# Digital_Attenuator.net
KiCad netlist of a schematic drawn in Altium Designer
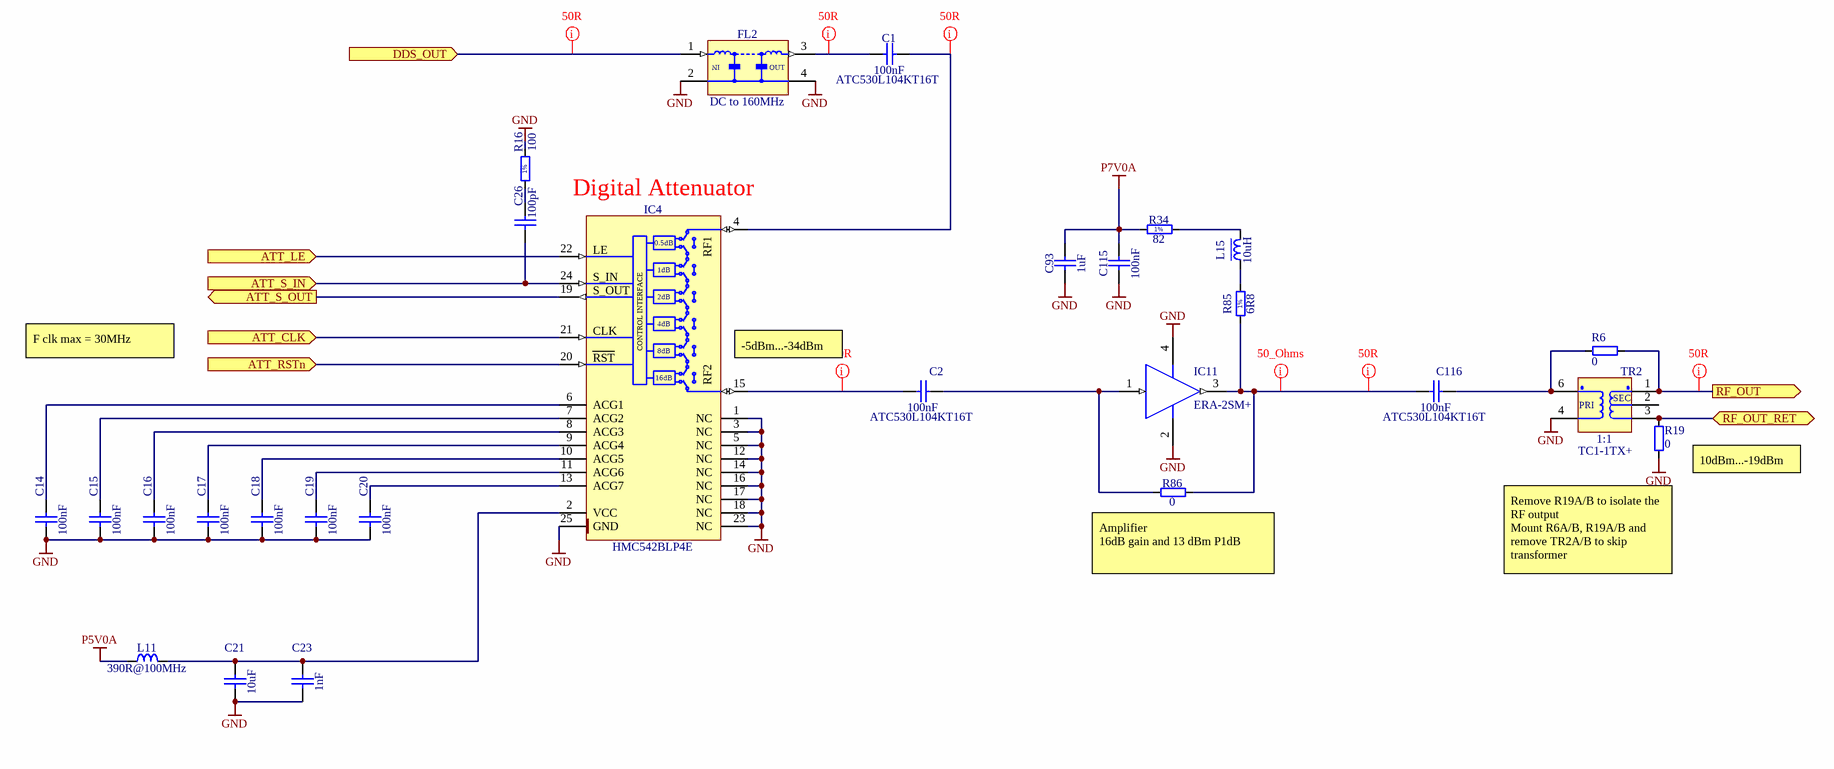
[diagram p0: Digital_Attenuator.SchDoc]

(export (version "E")
  (design (tool "Eeschema 10.0.6"))
  (components
    (comp (ref "C1")
      (value "100nF")
      (footprint "CAPC1005X70N")
      (description "Non-polarised capacitor")
      (fields
        (field (name "PART NUMBER") "CC0402_100NF_16V_10%_X7R_ATC_ATC530L")
        (field (name "VOLTAGE") "16V")
        (field (name "MANUFACTURER PART NUMBER") "ATC530L104KT16T")
        (field (name "AUTHOR") "CERN DEM BC")
      )
      (libsource (lib "Capacitors") (part "Capacitor - non polarized"))
    )
    (comp (ref "C2")
      (value "100nF")
      (footprint "CAPC1005X70N")
      (description "Non-polarised capacitor")
      (fields
        (field (name "PART NUMBER") "CC0402_100NF_16V_10%_X7R_ATC_ATC530L")
        (field (name "VOLTAGE") "16V")
        (field (name "MANUFACTURER PART NUMBER") "ATC530L104KT16T")
        (field (name "AUTHOR") "CERN DEM BC")
      )
      (libsource (lib "Capacitors") (part "Capacitor - non polarized"))
    )
    (comp (ref "C14")
      (value "100nF")
      (footprint "CAPC1005X55N")
      (description "Non-polarised capacitor")
      (fields
        (field (name "PART NUMBER") "CC0402_100NF_16V_10%_X5R")
        (field (name "VOLTAGE") "16V")
        (field (name "AUTHOR") "CERN DEM JLC")
      )
      (libsource (lib "Capacitors") (part "Capacitor - non polarized"))
    )
    (comp (ref "C15")
      (value "100nF")
      (footprint "CAPC1005X55N")
      (description "Non-polarised capacitor")
      (fields
        (field (name "PART NUMBER") "CC0402_100NF_16V_10%_X5R")
        (field (name "VOLTAGE") "16V")
        (field (name "AUTHOR") "CERN DEM JLC")
      )
      (libsource (lib "Capacitors") (part "Capacitor - non polarized"))
    )
    (comp (ref "C16")
      (value "100nF")
      (footprint "CAPC1005X55N")
      (description "Non-polarised capacitor")
      (fields
        (field (name "PART NUMBER") "CC0402_100NF_16V_10%_X5R")
        (field (name "VOLTAGE") "16V")
        (field (name "AUTHOR") "CERN DEM JLC")
      )
      (libsource (lib "Capacitors") (part "Capacitor - non polarized"))
    )
    (comp (ref "C17")
      (value "100nF")
      (footprint "CAPC1005X55N")
      (description "Non-polarised capacitor")
      (fields
        (field (name "PART NUMBER") "CC0402_100NF_16V_10%_X5R")
        (field (name "VOLTAGE") "16V")
        (field (name "AUTHOR") "CERN DEM JLC")
      )
      (libsource (lib "Capacitors") (part "Capacitor - non polarized"))
    )
    (comp (ref "C18")
      (value "100nF")
      (footprint "CAPC1005X55N")
      (description "Non-polarised capacitor")
      (fields
        (field (name "PART NUMBER") "CC0402_100NF_16V_10%_X5R")
        (field (name "VOLTAGE") "16V")
        (field (name "AUTHOR") "CERN DEM JLC")
      )
      (libsource (lib "Capacitors") (part "Capacitor - non polarized"))
    )
    (comp (ref "C19")
      (value "100nF")
      (footprint "CAPC1005X55N")
      (description "Non-polarised capacitor")
      (fields
        (field (name "PART NUMBER") "CC0402_100NF_16V_10%_X5R")
        (field (name "VOLTAGE") "16V")
        (field (name "AUTHOR") "CERN DEM JLC")
      )
      (libsource (lib "Capacitors") (part "Capacitor - non polarized"))
    )
    (comp (ref "C20")
      (value "100nF")
      (footprint "CAPC1005X55N")
      (description "Non-polarised capacitor")
      (fields
        (field (name "PART NUMBER") "CC0402_100NF_16V_10%_X5R")
        (field (name "VOLTAGE") "16V")
        (field (name "AUTHOR") "CERN DEM JLC")
      )
      (libsource (lib "Capacitors") (part "Capacitor - non polarized"))
    )
    (comp (ref "C21")
      (value "10uF")
      (footprint "CAPC1608X80N")
      (description "Non-polarised capacitor")
      (fields
        (field (name "PART NUMBER") "CC0603_10UF_16V_20%_X5R")
        (field (name "VOLTAGE") "16V")
        (field (name "AUTHOR") "CERN DEM MR")
      )
      (libsource (lib "Capacitors") (part "Capacitor - non polarized"))
    )
    (comp (ref "C23")
      (value "1nF")
      (footprint "CAPC1005X55N")
      (description "Non-polarised capacitor")
      (fields
        (field (name "PART NUMBER") "CC0402_1NF_50V_10%_X7R")
        (field (name "VOLTAGE") "50V")
        (field (name "AUTHOR") "CERN DEM JLC")
      )
      (libsource (lib "Capacitors") (part "Capacitor - non polarized"))
    )
    (comp (ref "C26")
      (value "100pF")
      (footprint "CAPC1005X55N")
      (description "Non-polarised capacitor")
      (fields
        (field (name "PART NUMBER") "CC0402_100PF_50V_5%_C0G")
        (field (name "VOLTAGE") "50V")
        (field (name "AUTHOR") "CERN DEM JLC")
      )
      (libsource (lib "Capacitors") (part "Capacitor - non polarized"))
    )
    (comp (ref "C93")
      (value "1uF")
      (footprint "CAPC2012X140N")
      (description "Non-polarised capacitor")
      (fields
        (field (name "PART NUMBER") "CC0805_1UF_35V_20%_X7R")
        (field (name "VOLTAGE") "35V")
        (field (name "AUTHOR") "CERN DEM JLC")
      )
      (libsource (lib "Capacitors") (part "Capacitor - non polarized"))
    )
    (comp (ref "C115")
      (value "100nF")
      (footprint "CAPC1005X55N")
      (description "Non-polarised capacitor")
      (fields
        (field (name "PART NUMBER") "CC0402_100NF_16V_10%_X5R")
        (field (name "VOLTAGE") "16V")
        (field (name "AUTHOR") "CERN DEM JLC")
      )
      (libsource (lib "Capacitors") (part "Capacitor - non polarized"))
    )
    (comp (ref "C116")
      (value "100nF")
      (footprint "CAPC1005X70N")
      (description "Non-polarised capacitor")
      (fields
        (field (name "PART NUMBER") "CC0402_100NF_16V_10%_X7R_ATC_ATC530L")
        (field (name "VOLTAGE") "16V")
        (field (name "MANUFACTURER PART NUMBER") "ATC530L104KT16T")
        (field (name "AUTHOR") "CERN DEM BC")
      )
      (libsource (lib "Capacitors") (part "Capacitor - non polarized"))
    )
    (comp (ref "FL2")
      (value "DC to 160MHz")
      (footprint "FIL_MINI-CIRCUITS_FV1206")
      (description "50 Ohms DC to 160MHz Low Pass Filter")
      (fields
        (field (name "PART NUMBER") "FIL_MINI-CIRCUITS_LFCN-160+")
        (field (name "MANUFACTURER") "MINI-CIRCUITS")
        (field (name "AUTHOR") "CERN DEM MR")
      )
      (libsource (lib "Inductors & Transformers") (part "FIL_MINI-CIRCUITS_LFCN-160+"))
    )
    (comp (ref "IC4")
      (value "HMC542BLP4E")
      (footprint "QFN50P400X400X100-25N-S295")
      (description "0.5dB LSB GaAs MMIC 6-bit Digital Serial Control Attenuator, DC - 4GHz")
      (fields (field (name "MANUFACTURER") "HITTITE MICROWAVE CORP") (field (name "AUTHOR") "CERN DEM JMW"))
      (libsource (lib "ICs And Semiconductors") (part "HMC542BLP4E"))
    )
    (comp (ref "IC11")
      (value "ERA-2SM+")
      (footprint "MINI-CIRCUITS_WW107")
      (description "Monolithic Amplifier")
      (fields (field (name "MANUFACTURER") "MINI-CIRCUITS") (field (name "AUTHOR") "CERN DEM JLC"))
      (libsource (lib "ICs And Semiconductors") (part "Monolithic Amplifier Type 1"))
    )
    (comp (ref "L11")
      (value "390R@100MHz")
      (footprint "INDC1608X95N")
      (description "Inductor")
      (fields
        (field (name "PART NUMBER") "IND0603_TDK_MPZ1608R391A")
        (field (name "POWER") "1.2A")
        (field (name "AUTHOR") "CERN DEM JLC")
      )
      (libsource (lib "Inductors & Transformers") (part "Inductor"))
    )
    (comp (ref "L15")
      (value "10uH")
      (footprint "IND_MURATA_LQH32C")
      (description "Inductor With Core")
      (fields
        (field (name "PART NUMBER") "IND_10UH_10%_MURATA_LQH32CN100K33L")
        (field (name "POWER") "450mA")
        (field (name "AUTHOR") "CERN DEM JLC")
      )
      (libsource (lib "Inductors & Transformers") (part "Inductor With Magnetic core"))
    )
    (comp (ref "R6")
      (value "0")
      (footprint "RESC1005X40N")
      (description "Resistor")
      (fields
        (field (name "PART NUMBER") "R0402_0R_JUMPER")
        (field (name "MANUFACTURER") "GENERIC")
        (field (name "AUTHOR") "CERN DEM JLC")
      )
      (libsource (lib "Resistors") (part "Resistor"))
    )
    (comp (ref "R16")
      (value "100")
      (footprint "RESC1005X40N")
      (description "Resistor - 1%")
      (fields
        (field (name "PART NUMBER") "R0402_100R_1%_0.0625W_100PPM")
        (field (name "POWER") "0.0625W")
        (field (name "AUTHOR") "CERN DEM JLC")
      )
      (libsource (lib "Resistors") (part "Resistor - 1%"))
    )
    (comp (ref "R19")
      (value "0")
      (footprint "RESC1005X40N")
      (description "Resistor")
      (fields
        (field (name "PART NUMBER") "R0402_0R_JUMPER")
        (field (name "MANUFACTURER") "GENERIC")
        (field (name "AUTHOR") "CERN DEM JLC")
      )
      (libsource (lib "Resistors") (part "Resistor"))
    )
    (comp (ref "R34")
      (value "82")
      (footprint "RESC3216X65N")
      (description "Resistor - 1%")
      (fields
        (field (name "PART NUMBER") "R1206_82R_1%_0.25W_100PPM")
        (field (name "POWER") "0.25W")
        (field (name "AUTHOR") "CERN DEM JLC")
      )
      (libsource (lib "Resistors") (part "Resistor - 1%"))
    )
    (comp (ref "R85")
      (value "6R8")
      (footprint "RESC1608X55N")
      (description "Resistor - 1%")
      (fields
        (field (name "PART NUMBER") "R0603_6R8_1%_0.1W_200PPM")
        (field (name "POWER") "0.1W")
        (field (name "AUTHOR") "CERN DEM JLC")
      )
      (libsource (lib "Resistors") (part "Resistor - 1%"))
    )
    (comp (ref "R86")
      (value "0")
      (footprint "RESC1608X55N")
      (description "Resistor")
      (fields
        (field (name "PART NUMBER") "R0603_0R_JUMPER")
        (field (name "MANUFACTURER") "GENERIC")
        (field (name "AUTHOR") "CERN DEM JLC")
      )
      (libsource (lib "Resistors") (part "Resistor"))
    )
    (comp (ref "TR2")
      (value "1:1")
      (footprint "XFMR_MINI-CIRCUITS_AT1521")
      (description "50 Ohms 3 to 300MHz RF Transformer")
      (fields
        (field (name "PART NUMBER") "XFMR_MINI-CIRCUITS_TC1-1TX+")
        (field (name "MANUFACTURER") "MINI-CIRCUITS")
        (field (name "MANUFACTURER PART NUMBER") "TC1-1TX+")
        (field (name "AUTHOR") "GK")
      )
      (libsource (lib "Inductors_Transformers") (part "XFMR_MINI-CIRCUITS_TC1-1TX+"))
    )
  )
  (nets
    (net (code "1") (name "/ATT_CLK") (class "Default")
      (node (ref "IC4") (pin "21") (pinfunction "SHIFT_CLOCK_21") (pintype "input"))
    )
    (net (code "2") (name "/ATT_LE") (class "Default")
      (node (ref "IC4") (pin "22") (pinfunction "LATCH_ENABLE_22") (pintype "input"))
    )
    (net (code "3") (name "/ATT_RSTn") (class "Default")
      (node (ref "IC4") (pin "20") (pinfunction "~{RESET}_20") (pintype "input"))
    )
    (net (code "4") (name "/ATT_S_IN") (class "Default")
      (node (ref "C26") (pin "2") (pinfunction "2_2") (pintype "passive"))
      (node (ref "IC4") (pin "24") (pinfunction "SERIAL_INPUT_24") (pintype "input"))
    )
    (net (code "5") (name "/ATT_S_OUT") (class "Default")
      (node (ref "IC4") (pin "19") (pinfunction "SERIAL_OUTPUT_19") (pintype "output"))
    )
    (net (code "6") (name "/DDS_OUT") (class "Default")
      (node (ref "FL2") (pin "1") (pinfunction "RFIN_1") (pintype "input"))
    )
    (net (code "7") (name "/RF_OUT") (class "Default")
      (node (ref "R6") (pin "1") (pinfunction "1_1") (pintype "passive"))
      (node (ref "TR2") (pin "1") (pinfunction "SDOT_1") (pintype "passive"))
    )
    (net (code "8") (name "/RF_OUT_RET") (class "Default")
      (node (ref "R19") (pin "2") (pinfunction "2_2") (pintype "passive"))
      (node (ref "TR2") (pin "3") (pinfunction "S_3") (pintype "passive"))
    )
    (net (code "9") (name "GND") (class "Default")
      (node (ref "C115") (pin "1") (pinfunction "1_1") (pintype "passive"))
      (node (ref "C14") (pin "1") (pinfunction "1_1") (pintype "passive"))
      (node (ref "C15") (pin "1") (pinfunction "1_1") (pintype "passive"))
      (node (ref "C16") (pin "1") (pinfunction "1_1") (pintype "passive"))
      (node (ref "C17") (pin "1") (pinfunction "1_1") (pintype "passive"))
      (node (ref "C18") (pin "1") (pinfunction "1_1") (pintype "passive"))
      (node (ref "C19") (pin "1") (pinfunction "1_1") (pintype "passive"))
      (node (ref "C20") (pin "1") (pinfunction "1_1") (pintype "passive"))
      (node (ref "C21") (pin "1") (pinfunction "1_1") (pintype "passive"))
      (node (ref "C23") (pin "1") (pinfunction "1_1") (pintype "passive"))
      (node (ref "C93") (pin "1") (pinfunction "1_1") (pintype "passive"))
      (node (ref "FL2") (pin "2") (pinfunction "GND_2") (pintype "power_in"))
      (node (ref "FL2") (pin "4") (pinfunction "GND_4") (pintype "power_in"))
      (node (ref "IC11") (pin "2") (pinfunction "GND_2") (pintype "power_in"))
      (node (ref "IC11") (pin "4") (pinfunction "GND_4") (pintype "power_in"))
      (node (ref "IC4") (pin "1") (pinfunction "NC_1") (pintype "passive"))
      (node (ref "IC4") (pin "12") (pinfunction "NC_12") (pintype "passive"))
      (node (ref "IC4") (pin "14") (pinfunction "NC_14") (pintype "passive"))
      (node (ref "IC4") (pin "16") (pinfunction "NC_16") (pintype "passive"))
      (node (ref "IC4") (pin "17") (pinfunction "NC_17") (pintype "passive"))
      (node (ref "IC4") (pin "18") (pinfunction "NC_18") (pintype "passive"))
      (node (ref "IC4") (pin "23") (pinfunction "NC_23") (pintype "passive"))
      (node (ref "IC4") (pin "25") (pinfunction "GND_25") (pintype "power_in"))
      (node (ref "IC4") (pin "3") (pinfunction "NC_3") (pintype "passive"))
      (node (ref "IC4") (pin "5") (pinfunction "NC_5") (pintype "passive"))
      (node (ref "R16") (pin "2") (pinfunction "2_2") (pintype "passive"))
      (node (ref "R19") (pin "1") (pinfunction "1_1") (pintype "passive"))
      (node (ref "TR2") (pin "4") (pinfunction "P_4") (pintype "passive"))
    )
    (net (code "10") (name "Net-(C26-Pad1)") (class "Default")
      (node (ref "C26") (pin "1") (pinfunction "1_1") (pintype "passive"))
      (node (ref "R16") (pin "1") (pinfunction "1_1") (pintype "passive"))
    )
    (net (code "11") (name "Net-(FL2-RFOUT)") (class "Default")
      (node (ref "C1") (pin "1") (pinfunction "1_1") (pintype "passive"))
      (node (ref "FL2") (pin "3") (pinfunction "RFOUT_3") (pintype "output"))
    )
    (net (code "12") (name "Net-(IC4-ACG1)") (class "Default")
      (node (ref "C14") (pin "2") (pinfunction "2_2") (pintype "passive"))
      (node (ref "IC4") (pin "6") (pinfunction "ACG1_6") (pintype "passive"))
    )
    (net (code "13") (name "Net-(IC4-ACG2)") (class "Default")
      (node (ref "C15") (pin "2") (pinfunction "2_2") (pintype "passive"))
      (node (ref "IC4") (pin "7") (pinfunction "ACG2_7") (pintype "passive"))
    )
    (net (code "14") (name "Net-(IC4-ACG3)") (class "Default")
      (node (ref "C16") (pin "2") (pinfunction "2_2") (pintype "passive"))
      (node (ref "IC4") (pin "8") (pinfunction "ACG3_8") (pintype "passive"))
    )
    (net (code "15") (name "Net-(IC4-ACG4)") (class "Default")
      (node (ref "C17") (pin "2") (pinfunction "2_2") (pintype "passive"))
      (node (ref "IC4") (pin "9") (pinfunction "ACG4_9") (pintype "passive"))
    )
    (net (code "16") (name "Net-(IC4-ACG5)") (class "Default")
      (node (ref "C18") (pin "2") (pinfunction "2_2") (pintype "passive"))
      (node (ref "IC4") (pin "10") (pinfunction "ACG5_10") (pintype "passive"))
    )
    (net (code "17") (name "Net-(IC4-ACG6)") (class "Default")
      (node (ref "C19") (pin "2") (pinfunction "2_2") (pintype "passive"))
      (node (ref "IC4") (pin "11") (pinfunction "ACG6_11") (pintype "passive"))
    )
    (net (code "18") (name "Net-(IC4-ACG7)") (class "Default")
      (node (ref "C20") (pin "2") (pinfunction "2_2") (pintype "passive"))
      (node (ref "IC4") (pin "13") (pinfunction "ACG7_13") (pintype "passive"))
    )
    (net (code "19") (name "Net-(IC4-RF1)") (class "Default")
      (node (ref "C1") (pin "2") (pinfunction "2_2") (pintype "passive"))
      (node (ref "IC4") (pin "4") (pinfunction "RF1_4") (pintype "bidirectional"))
    )
    (net (code "20") (name "Net-(IC4-RF2)") (class "Default")
      (node (ref "C2") (pin "1") (pinfunction "1_1") (pintype "passive"))
      (node (ref "IC4") (pin "15") (pinfunction "RF2_15") (pintype "bidirectional"))
    )
    (net (code "21") (name "Net-(IC4-VCC)") (class "Default")
      (node (ref "C21") (pin "2") (pinfunction "2_2") (pintype "passive"))
      (node (ref "C23") (pin "2") (pinfunction "2_2") (pintype "passive"))
      (node (ref "IC4") (pin "2") (pinfunction "VCC_2") (pintype "power_in"))
      (node (ref "L11") (pin "2") (pinfunction "2_2") (pintype "passive"))
    )
    (net (code "22") (name "Net-(IC11-RF_IN)") (class "Default")
      (node (ref "C2") (pin "2") (pinfunction "2_2") (pintype "passive"))
      (node (ref "IC11") (pin "1") (pinfunction "RF_IN_1") (pintype "input"))
      (node (ref "R86") (pin "1") (pinfunction "1_1") (pintype "passive"))
    )
    (net (code "23") (name "Net-(IC11-RF_OUT)") (class "Default")
      (node (ref "C116") (pin "1") (pinfunction "1_1") (pintype "passive"))
      (node (ref "IC11") (pin "3") (pinfunction "RF_OUT_3") (pintype "output"))
      (node (ref "R85") (pin "1") (pinfunction "1_1") (pintype "passive"))
      (node (ref "R86") (pin "2") (pinfunction "2_2") (pintype "passive"))
    )
    (net (code "24") (name "Net-(L15-Pad1)") (class "Default")
      (node (ref "L15") (pin "1") (pinfunction "1_1") (pintype "passive"))
      (node (ref "R85") (pin "2") (pinfunction "2_2") (pintype "passive"))
    )
    (net (code "25") (name "Net-(L15-Pad2)") (class "Default")
      (node (ref "L15") (pin "2") (pinfunction "2_2") (pintype "passive"))
      (node (ref "R34") (pin "2") (pinfunction "2_2") (pintype "passive"))
    )
    (net (code "26") (name "Net-(TR2-PDOT)") (class "Default")
      (node (ref "C116") (pin "2") (pinfunction "2_2") (pintype "passive"))
      (node (ref "R6") (pin "2") (pinfunction "2_2") (pintype "passive"))
      (node (ref "TR2") (pin "6") (pinfunction "PDOT_6") (pintype "passive"))
    )
    (net (code "27") (name "P5V0A") (class "Default")
      (node (ref "L11") (pin "1") (pinfunction "1_1") (pintype "passive"))
    )
    (net (code "28") (name "P7V0A") (class "Default")
      (node (ref "C115") (pin "2") (pinfunction "2_2") (pintype "passive"))
      (node (ref "C93") (pin "2") (pinfunction "2_2") (pintype "passive"))
      (node (ref "R34") (pin "1") (pinfunction "1_1") (pintype "passive"))
    )
    (net (code "29") (name "unconnected-(TR2-NC-Pad2)") (class "Default")
      (node (ref "TR2") (pin "2") (pinfunction "NC_2") (pintype "passive"))
    )
  )
)
